# magnetorquer_board.net
KiCad netlist of a schematic drawn in EAGLE
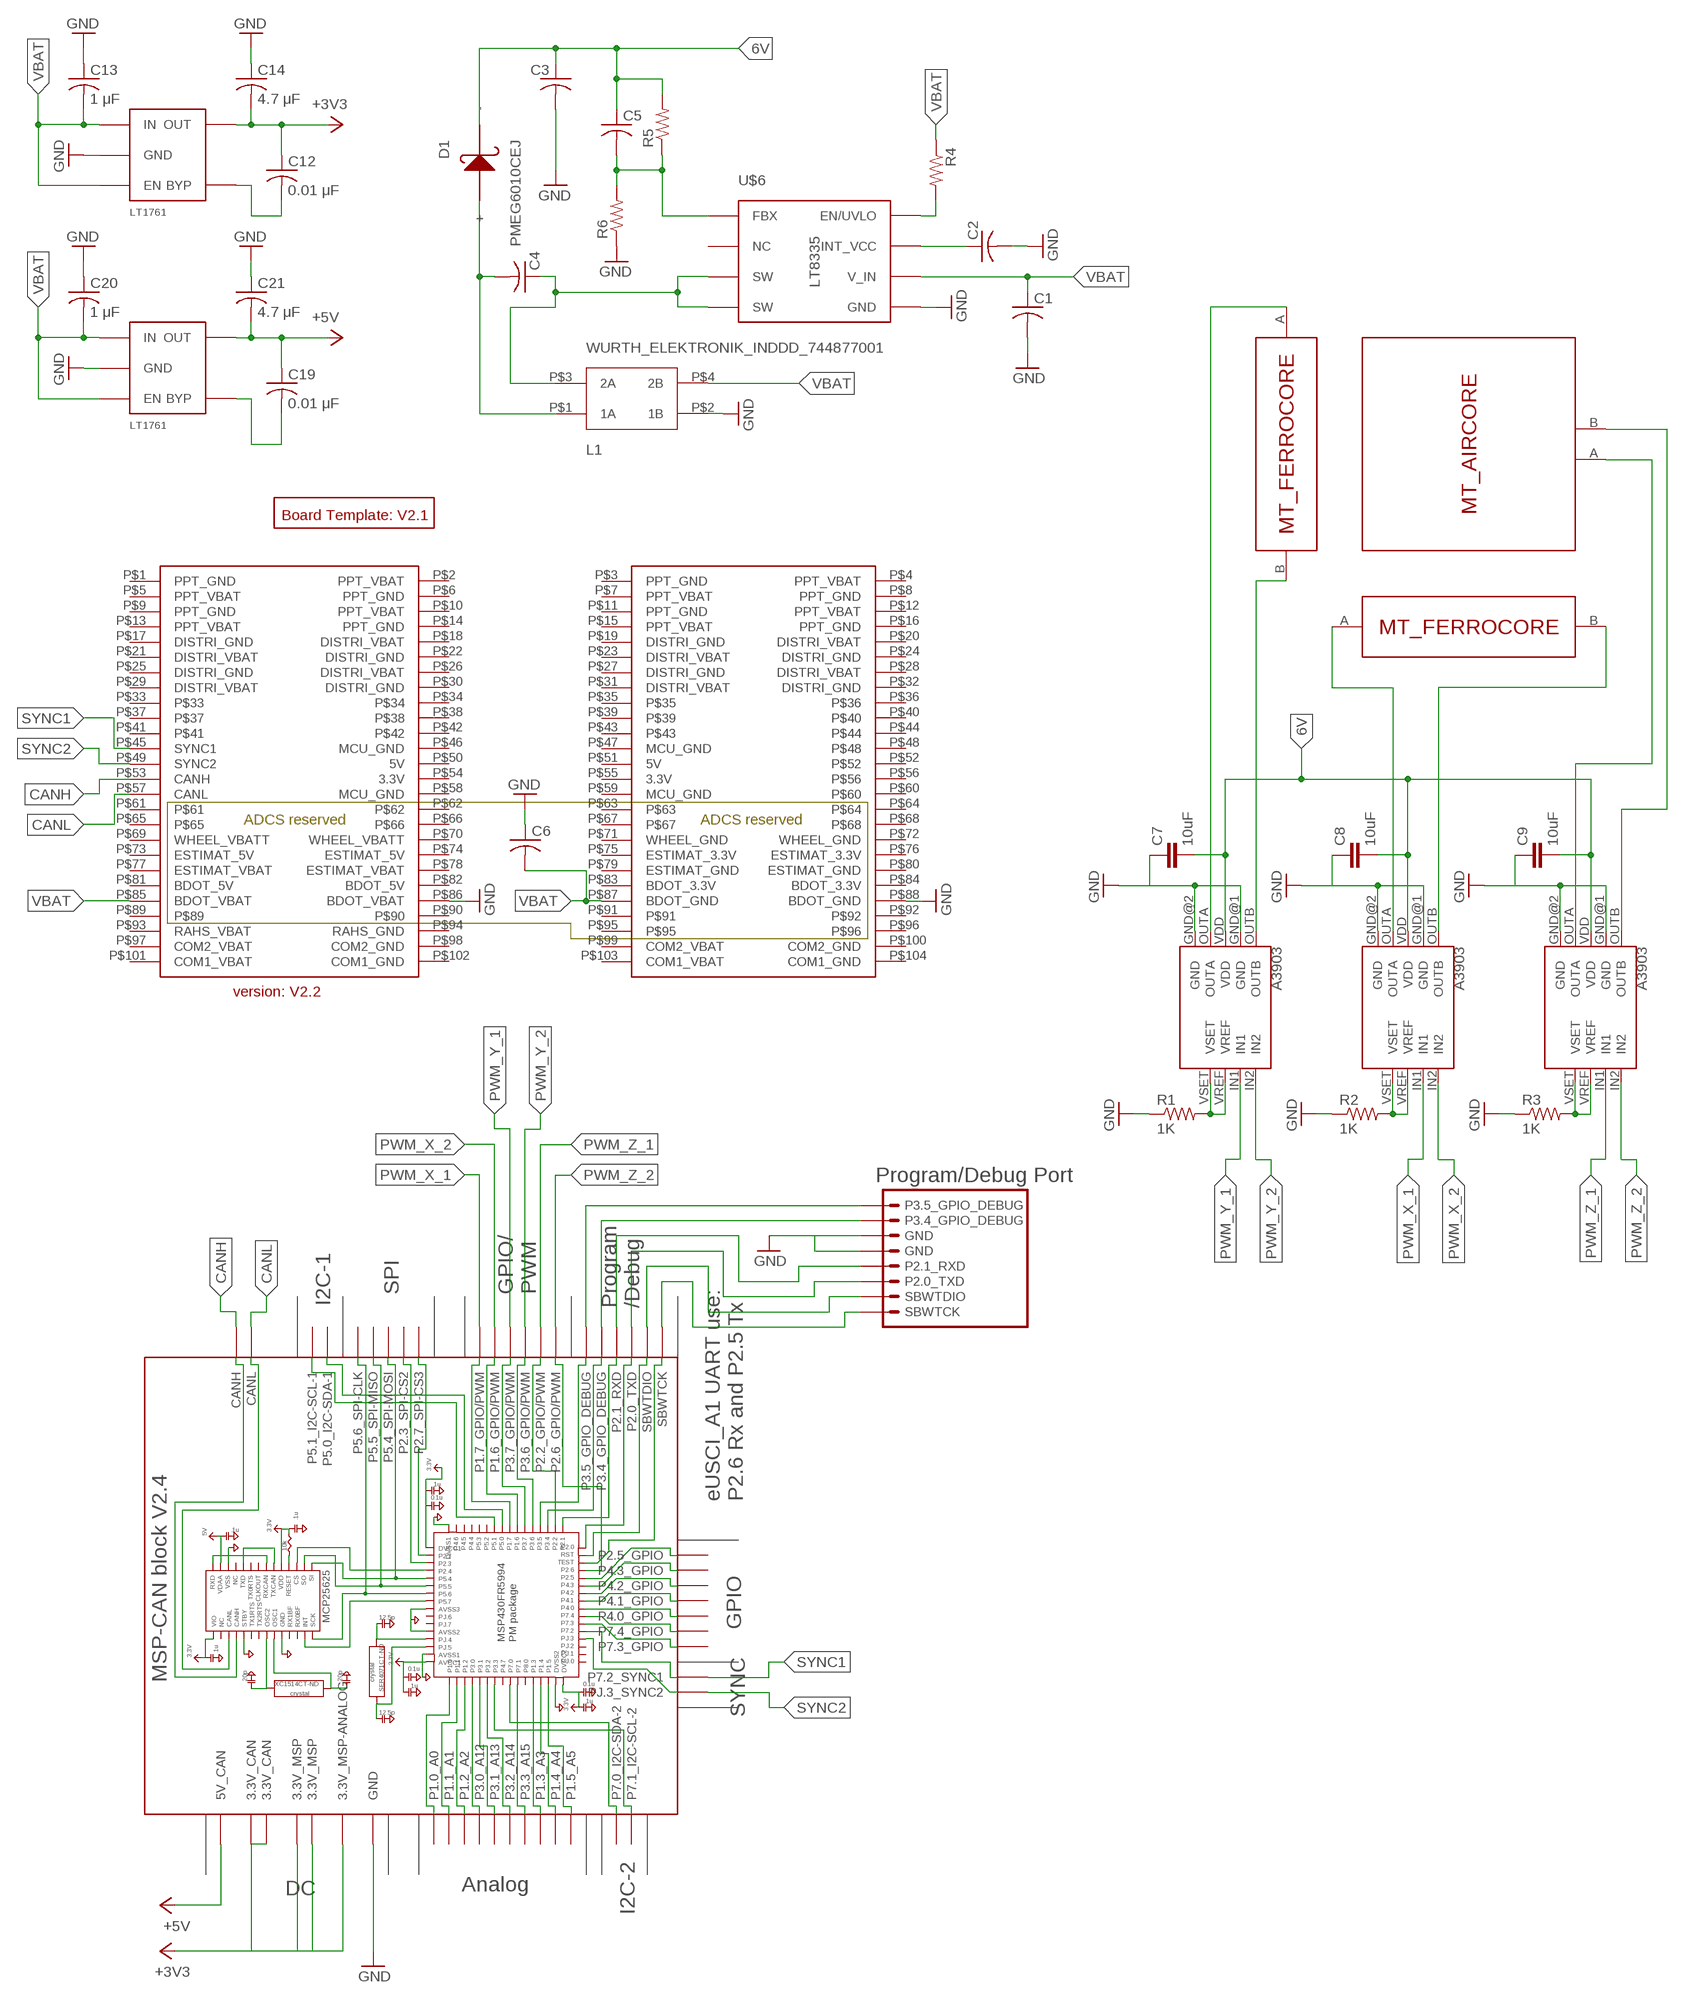
[diagram p0: schematic, sheet 1]

(export (version "E")
  (design (tool "Eeschema 10.0.6"))
  (components
    (comp (ref "C1")
      (value "C-USC0805")
      (footprint "eagle-import:C0805")
      (libsource (lib "eagle-import") (part "C-USC0805"))
    )
    (comp (ref "C2")
      (value "C-USC0805")
      (footprint "eagle-import:C0805")
      (libsource (lib "eagle-import") (part "C-USC0805"))
    )
    (comp (ref "C3")
      (value "C-USC0805")
      (footprint "eagle-import:C0805")
      (libsource (lib "eagle-import") (part "C-USC0805"))
    )
    (comp (ref "C4")
      (value "C-USC0805")
      (footprint "eagle-import:C0805")
      (libsource (lib "eagle-import") (part "C-USC0805"))
    )
    (comp (ref "C5")
      (value "C-USC0805")
      (footprint "eagle-import:C0805")
      (libsource (lib "eagle-import") (part "C-USC0805"))
    )
    (comp (ref "C6")
      (value "C-USC0805")
      (footprint "eagle-import:C0805")
      (libsource (lib "eagle-import") (part "C-USC0805"))
    )
    (comp (ref "C7")
      (value "10uF")
      (footprint "eagle-import:C0805")
      (libsource (lib "eagle-import") (part "C-EUC0805"))
    )
    (comp (ref "C8")
      (value "10uF")
      (footprint "eagle-import:C0805")
      (libsource (lib "eagle-import") (part "C-EUC0805"))
    )
    (comp (ref "C9")
      (value "10uF")
      (footprint "eagle-import:C0805")
      (libsource (lib "eagle-import") (part "C-EUC0805"))
    )
    (comp (ref "C12")
      (value "0.01 μF")
      (footprint "eagle-import:C0805")
      (libsource (lib "eagle-import") (part "C-USC0805"))
    )
    (comp (ref "C13")
      (value "1 μF")
      (footprint "eagle-import:C0805")
      (libsource (lib "eagle-import") (part "C-USC0805"))
    )
    (comp (ref "C14")
      (value "4.7 μF")
      (footprint "eagle-import:C0805")
      (libsource (lib "eagle-import") (part "C-USC0805"))
    )
    (comp (ref "C19")
      (value "0.01 μF")
      (footprint "eagle-import:C0805")
      (libsource (lib "eagle-import") (part "C-USC0805"))
    )
    (comp (ref "C20")
      (value "1 μF")
      (footprint "eagle-import:C0805")
      (libsource (lib "eagle-import") (part "C-USC0805"))
    )
    (comp (ref "C21")
      (value "4.7 μF")
      (footprint "eagle-import:C0805")
      (libsource (lib "eagle-import") (part "C-USC0805"))
    )
    (comp (ref "D1")
      (value "PMEG6010CEJ")
      (footprint "eagle-import:SC-90")
      (libsource (lib "eagle-import") (part "PMEG6010CEJ"))
    )
    (comp (ref "L1")
      (value "WURTH_ELEKTRONIK_INDDD_744877001")
      (footprint "eagle-import:WURTH_ELEKTRONIK_INDDD_744877001")
      (libsource (lib "eagle-import") (part "WURTH_ELEKTRONIK_INDDD_744877001"))
    )
    (comp (ref "LDO_3V1")
      (value "LINEAR_LDO_LT1761-X")
      (footprint "eagle-import:SOT-23-5")
      (libsource (lib "eagle-import") (part "LINEAR_LDO_LT1761-X"))
    )
    (comp (ref "LDO_5V1")
      (value "LINEAR_LDO_LT1761-X")
      (footprint "eagle-import:SOT-23-5")
      (libsource (lib "eagle-import") (part "LINEAR_LDO_LT1761-X"))
    )
    (comp (ref "R1")
      (value "1K")
      (footprint "eagle-import:R0603")
      (libsource (lib "eagle-import") (part "R-US_R0603"))
    )
    (comp (ref "R2")
      (value "1K")
      (footprint "eagle-import:R0603")
      (libsource (lib "eagle-import") (part "R-US_R0603"))
    )
    (comp (ref "R3")
      (value "1K")
      (footprint "eagle-import:R0603")
      (libsource (lib "eagle-import") (part "R-US_R0603"))
    )
    (comp (ref "R4")
      (value "R-US_R0805")
      (footprint "eagle-import:R0805")
      (libsource (lib "eagle-import") (part "R-US_R0805"))
    )
    (comp (ref "R5")
      (value "R-US_R0805")
      (footprint "eagle-import:R0805")
      (libsource (lib "eagle-import") (part "R-US_R0805"))
    )
    (comp (ref "R6")
      (value "R-US_R0805")
      (footprint "eagle-import:R0805")
      (libsource (lib "eagle-import") (part "R-US_R0805"))
    )
    (comp (ref "U$1")
      (value "PC104_CONNECTOR")
      (footprint "eagle-import:PC104_CONNECTOR")
      (libsource (lib "eagle-import") (part "PC104_CONNECTOR"))
    )
    (comp (ref "U$2")
      (value "BOARD_TEMPLATE")
      (footprint "eagle-import:BOARD_TEMPLATE")
      (libsource (lib "eagle-import") (part "BOARD_TEMPLATE"))
    )
    (comp (ref "U$3")
      (value "MT_AIRCORE")
      (footprint "eagle-import:MT_AIRCORE")
      (libsource (lib "eagle-import") (part "MT_AIRCORE"))
    )
    (comp (ref "U$4")
      (value "MT_FERROCORE")
      (footprint "eagle-import:MT_FERROCORE")
      (libsource (lib "eagle-import") (part "MT_FERROCORE"))
    )
    (comp (ref "U$5")
      (value "MT_FERROCORE")
      (footprint "eagle-import:MT_FERROCORE")
      (libsource (lib "eagle-import") (part "MT_FERROCORE"))
    )
    (comp (ref "U$6")
      (value "LT8335")
      (footprint "eagle-import:DDB")
      (libsource (lib "eagle-import") (part "LT8335"))
    )
    (comp (ref "U$7")
      (value "MSP-CAN_BLOCK")
      (footprint "eagle-import:MSP-CAN_BLOCK")
      (libsource (lib "eagle-import") (part "MSP-CAN_BLOCK"))
    )
    (comp (ref "U$8")
      (value "PROGRAM/DEBUG_PORT")
      (footprint "eagle-import:1X08_CONNECTOR")
      (libsource (lib "eagle-import") (part "PROGRAM/DEBUG_PORT"))
    )
    (comp (ref "U1")
      (value "A3903")
      (footprint "eagle-import:DFN-8EE")
      (libsource (lib "eagle-import") (part "A3903"))
    )
    (comp (ref "U2")
      (value "A3903")
      (footprint "eagle-import:DFN-8EE")
      (libsource (lib "eagle-import") (part "A3903"))
    )
    (comp (ref "U3")
      (value "A3903")
      (footprint "eagle-import:DFN-8EE")
      (libsource (lib "eagle-import") (part "A3903"))
    )
  )
  (nets
    (net (code "1") (name "+3V3") (class "Default")
      (node (ref "C12") (pin "1") (pinfunction "1_1") (pintype "passive"))
      (node (ref "C14") (pin "2") (pinfunction "2_2") (pintype "passive"))
      (node (ref "LDO_3V1") (pin "P$5") (pinfunction "OUT_P$5") (pintype "bidirectional"))
      (node (ref "U$7") (pin "3.3V@CAN1") (pinfunction "3.3V_CAN_3.3V@CAN1") (pintype "bidirectional"))
      (node (ref "U$7") (pin "3.3V@CAN2") (pinfunction "3.3V_CAN_3.3V@CAN2") (pintype "bidirectional"))
      (node (ref "U$7") (pin "3.3V@MSP1") (pinfunction "3.3V_MSP_3.3V@MSP1") (pintype "bidirectional"))
      (node (ref "U$7") (pin "3.3V@MSP2") (pinfunction "3.3V_MSP_3.3V@MSP2") (pintype "bidirectional"))
      (node (ref "U$7") (pin "3.3V_ANALOG@MSP2") (pinfunction "3.3V_MSP-ANALOG_3.3V_ANALOG@MSP2") (pintype "bidirectional"))
    )
    (net (code "2") (name "+5V") (class "Default")
      (node (ref "C19") (pin "1") (pinfunction "1_1") (pintype "passive"))
      (node (ref "C21") (pin "2") (pinfunction "2_2") (pintype "passive"))
      (node (ref "LDO_5V1") (pin "P$5") (pinfunction "OUT_P$5") (pintype "bidirectional"))
      (node (ref "U$7") (pin "5V") (pinfunction "5V_CAN_5V") (pintype "bidirectional"))
    )
    (net (code "3") (name "6V") (class "Default")
      (node (ref "C3") (pin "1") (pinfunction "1_1") (pintype "passive"))
      (node (ref "C5") (pin "1") (pinfunction "1_1") (pintype "passive"))
      (node (ref "C7") (pin "2") (pinfunction "2_2") (pintype "passive"))
      (node (ref "C8") (pin "2") (pinfunction "2_2") (pintype "passive"))
      (node (ref "C9") (pin "2") (pinfunction "2_2") (pintype "passive"))
      (node (ref "D1") (pin "P$2") (pinfunction "-_P$2") (pintype "bidirectional"))
      (node (ref "R5") (pin "2") (pinfunction "2_2") (pintype "passive"))
      (node (ref "U1") (pin "VDD") (pinfunction "VDD_VDD") (pintype "power_in"))
      (node (ref "U2") (pin "VDD") (pinfunction "VDD_VDD") (pintype "power_in"))
      (node (ref "U3") (pin "VDD") (pinfunction "VDD_VDD") (pintype "power_in"))
    )
    (net (code "4") (name "CANH") (class "Default")
      (node (ref "U$1") (pin "P$53") (pinfunction "CANH_P$53") (pintype "bidirectional"))
      (node (ref "U$7") (pin "CANH") (pinfunction "CANH_CANH") (pintype "bidirectional"))
    )
    (net (code "5") (name "CANL") (class "Default")
      (node (ref "U$1") (pin "P$57") (pinfunction "CANL_P$57") (pintype "bidirectional"))
      (node (ref "U$7") (pin "CANL") (pinfunction "CANL_CANL") (pintype "bidirectional"))
    )
    (net (code "6") (name "GND") (class "Default")
      (node (ref "C1") (pin "2") (pinfunction "2_2") (pintype "passive"))
      (node (ref "C13") (pin "1") (pinfunction "1_1") (pintype "passive"))
      (node (ref "C14") (pin "1") (pinfunction "1_1") (pintype "passive"))
      (node (ref "C2") (pin "2") (pinfunction "2_2") (pintype "passive"))
      (node (ref "C20") (pin "1") (pinfunction "1_1") (pintype "passive"))
      (node (ref "C21") (pin "1") (pinfunction "1_1") (pintype "passive"))
      (node (ref "C3") (pin "2") (pinfunction "2_2") (pintype "passive"))
      (node (ref "C6") (pin "1") (pinfunction "1_1") (pintype "passive"))
      (node (ref "C7") (pin "1") (pinfunction "1_1") (pintype "passive"))
      (node (ref "C8") (pin "1") (pinfunction "1_1") (pintype "passive"))
      (node (ref "C9") (pin "1") (pinfunction "1_1") (pintype "passive"))
      (node (ref "L1") (pin "P$2") (pinfunction "1B_P$2") (pintype "bidirectional"))
      (node (ref "LDO_3V1") (pin "P$2") (pinfunction "GND_P$2") (pintype "bidirectional"))
      (node (ref "LDO_5V1") (pin "P$2") (pinfunction "GND_P$2") (pintype "bidirectional"))
      (node (ref "R1") (pin "1") (pinfunction "1_1") (pintype "passive"))
      (node (ref "R2") (pin "1") (pinfunction "1_1") (pintype "passive"))
      (node (ref "R3") (pin "1") (pinfunction "1_1") (pintype "passive"))
      (node (ref "R6") (pin "1") (pinfunction "1_1") (pintype "passive"))
      (node (ref "U$1") (pin "P$86") (pinfunction "BDOT_VBAT_P$86") (pintype "bidirectional"))
      (node (ref "U$1") (pin "P$88") (pinfunction "BDOT_GND_P$88") (pintype "bidirectional"))
      (node (ref "U$6") (pin "GND") (pinfunction "GND_GND") (pintype "bidirectional"))
      (node (ref "U$6") (pin "P$5") (pinfunction "GND_P$5") (pintype "bidirectional"))
      (node (ref "U$7") (pin "GND@1") (pinfunction "GND_GND@1") (pintype "bidirectional"))
      (node (ref "U$7") (pin "GND@10") (pinfunction "GND_GND@10") (pintype "bidirectional"))
      (node (ref "U$7") (pin "GND@11") (pinfunction "GND_GND@11") (pintype "bidirectional"))
      (node (ref "U$7") (pin "GND@12") (pinfunction "GND_GND@12") (pintype "bidirectional"))
      (node (ref "U$7") (pin "GND@13") (pinfunction "GND_GND@13") (pintype "bidirectional"))
      (node (ref "U$7") (pin "GND@14") (pinfunction "GND_GND@14") (pintype "bidirectional"))
      (node (ref "U$7") (pin "GND@15") (pinfunction "GND_GND@15") (pintype "bidirectional"))
      (node (ref "U$7") (pin "GND@16") (pinfunction "GND_GND@16") (pintype "bidirectional"))
      (node (ref "U$7") (pin "GND@17") (pinfunction "GND_GND@17") (pintype "bidirectional"))
      (node (ref "U$7") (pin "GND@2") (pinfunction "GND_GND@2") (pintype "bidirectional"))
      (node (ref "U$7") (pin "GND@26") (pinfunction "GND_GND@26") (pintype "bidirectional"))
      (node (ref "U$7") (pin "GND@3") (pinfunction "GND_GND@3") (pintype "bidirectional"))
      (node (ref "U$7") (pin "GND@4") (pinfunction "GND_GND@4") (pintype "bidirectional"))
      (node (ref "U$7") (pin "GND@5") (pinfunction "GND_GND@5") (pintype "bidirectional"))
      (node (ref "U$7") (pin "GND@7") (pinfunction "GND_GND@7") (pintype "bidirectional"))
      (node (ref "U$7") (pin "GND@8") (pinfunction "GND_GND@8") (pintype "bidirectional"))
      (node (ref "U$7") (pin "GND@9") (pinfunction "GND_GND@9") (pintype "bidirectional"))
      (node (ref "U$8") (pin "5") (pinfunction "GND_5") (pintype "bidirectional"))
      (node (ref "U$8") (pin "6") (pinfunction "GND_6") (pintype "bidirectional"))
      (node (ref "U1") (pin "GND@1") (pinfunction "GND_GND@1") (pintype "power_in"))
      (node (ref "U1") (pin "GND@2") (pinfunction "GND_GND@2") (pintype "power_in"))
      (node (ref "U2") (pin "GND@1") (pinfunction "GND_GND@1") (pintype "power_in"))
      (node (ref "U2") (pin "GND@2") (pinfunction "GND_GND@2") (pintype "power_in"))
      (node (ref "U3") (pin "GND@1") (pinfunction "GND_GND@1") (pintype "power_in"))
      (node (ref "U3") (pin "GND@2") (pinfunction "GND_GND@2") (pintype "power_in"))
    )
    (net (code "7") (name "Net-(D1-+)") (class "Default")
      (node (ref "C4") (pin "2") (pinfunction "2_2") (pintype "passive"))
      (node (ref "D1") (pin "P$1") (pinfunction "+_P$1") (pintype "bidirectional"))
      (node (ref "L1") (pin "P$1") (pinfunction "1A_P$1") (pintype "bidirectional"))
    )
    (net (code "8") (name "Net-(L1-2A)") (class "Default")
      (node (ref "C4") (pin "1") (pinfunction "1_1") (pintype "passive"))
      (node (ref "L1") (pin "P$3") (pinfunction "2A_P$3") (pintype "bidirectional"))
      (node (ref "U$6") (pin "P$3") (pinfunction "SW_P$3") (pintype "bidirectional"))
      (node (ref "U$6") (pin "P$4") (pinfunction "SW_P$4") (pintype "bidirectional"))
    )
    (net (code "9") (name "Net-(LDO_3V1-BYP)") (class "Default")
      (node (ref "C12") (pin "2") (pinfunction "2_2") (pintype "passive"))
      (node (ref "LDO_3V1") (pin "P$4") (pinfunction "BYP_P$4") (pintype "bidirectional"))
    )
    (net (code "10") (name "Net-(LDO_5V1-BYP)") (class "Default")
      (node (ref "C19") (pin "2") (pinfunction "2_2") (pintype "passive"))
      (node (ref "LDO_5V1") (pin "P$4") (pinfunction "BYP_P$4") (pintype "bidirectional"))
    )
    (net (code "11") (name "Net-(R1-Pad2)") (class "Default")
      (node (ref "R1") (pin "2") (pinfunction "2_2") (pintype "passive"))
      (node (ref "U1") (pin "VREF") (pinfunction "VREF_VREF") (pintype "power_in"))
      (node (ref "U1") (pin "VSET") (pinfunction "VSET_VSET") (pintype "bidirectional"))
    )
    (net (code "12") (name "Net-(R2-Pad2)") (class "Default")
      (node (ref "R2") (pin "2") (pinfunction "2_2") (pintype "passive"))
      (node (ref "U2") (pin "VREF") (pinfunction "VREF_VREF") (pintype "power_in"))
      (node (ref "U2") (pin "VSET") (pinfunction "VSET_VSET") (pintype "bidirectional"))
    )
    (net (code "13") (name "Net-(R3-Pad2)") (class "Default")
      (node (ref "R3") (pin "2") (pinfunction "2_2") (pintype "passive"))
      (node (ref "U3") (pin "VREF") (pinfunction "VREF_VREF") (pintype "power_in"))
      (node (ref "U3") (pin "VSET") (pinfunction "VSET_VSET") (pintype "bidirectional"))
    )
    (net (code "14") (name "Net-(U$3-PadA)") (class "Default")
      (node (ref "U$3") (pin "A") (pinfunction "A_A") (pintype "bidirectional"))
      (node (ref "U3") (pin "OUTA") (pinfunction "OUTA_OUTA") (pintype "output"))
    )
    (net (code "15") (name "Net-(U$3-PadB)") (class "Default")
      (node (ref "U$3") (pin "B") (pinfunction "B_B") (pintype "bidirectional"))
      (node (ref "U3") (pin "OUTB") (pinfunction "OUTB_OUTB") (pintype "output"))
    )
    (net (code "16") (name "Net-(U$4-PadA)") (class "Default")
      (node (ref "U$4") (pin "A") (pinfunction "A_A") (pintype "bidirectional"))
      (node (ref "U1") (pin "OUTA") (pinfunction "OUTA_OUTA") (pintype "output"))
    )
    (net (code "17") (name "Net-(U$4-PadB)") (class "Default")
      (node (ref "U$4") (pin "B") (pinfunction "B_B") (pintype "bidirectional"))
      (node (ref "U1") (pin "OUTB") (pinfunction "OUTB_OUTB") (pintype "output"))
    )
    (net (code "18") (name "Net-(U$5-PadA)") (class "Default")
      (node (ref "U$5") (pin "A") (pinfunction "A_A") (pintype "bidirectional"))
      (node (ref "U2") (pin "OUTA") (pinfunction "OUTA_OUTA") (pintype "output"))
    )
    (net (code "19") (name "Net-(U$5-PadB)") (class "Default")
      (node (ref "U$5") (pin "B") (pinfunction "B_B") (pintype "bidirectional"))
      (node (ref "U2") (pin "OUTB") (pinfunction "OUTB_OUTB") (pintype "output"))
    )
    (net (code "20") (name "Net-(U$6-EN{slash}UVLO)") (class "Default")
      (node (ref "R4") (pin "2") (pinfunction "2_2") (pintype "passive"))
      (node (ref "U$6") (pin "P$8") (pinfunction "EN/UVLO_P$8") (pintype "bidirectional"))
    )
    (net (code "21") (name "Net-(U$6-FBX)") (class "Default")
      (node (ref "C5") (pin "2") (pinfunction "2_2") (pintype "passive"))
      (node (ref "R5") (pin "1") (pinfunction "1_1") (pintype "passive"))
      (node (ref "R6") (pin "2") (pinfunction "2_2") (pintype "passive"))
      (node (ref "U$6") (pin "P$1") (pinfunction "FBX_P$1") (pintype "bidirectional"))
    )
    (net (code "22") (name "Net-(U$6-INT_VCC)") (class "Default")
      (node (ref "C2") (pin "1") (pinfunction "1_1") (pintype "passive"))
      (node (ref "U$6") (pin "P$7") (pinfunction "INT_VCC_P$7") (pintype "bidirectional"))
    )
    (net (code "23") (name "Net-(U$7-PadSBWTCK)") (class "Default")
      (node (ref "U$7") (pin "SBWTCK") (pinfunction "SBWTCK_SBWTCK") (pintype "bidirectional"))
      (node (ref "U$8") (pin "SBWTCK") (pinfunction "SBWTCK_SBWTCK") (pintype "bidirectional"))
    )
    (net (code "24") (name "Net-(U$8-P2.0_TXD)") (class "Default")
      (node (ref "U$7") (pin "P2.0_TXD") (pinfunction "P2.0_TXD_P2.0_TXD") (pintype "bidirectional"))
      (node (ref "U$8") (pin "3") (pinfunction "P2.0_TXD_3") (pintype "bidirectional"))
    )
    (net (code "25") (name "Net-(U$8-P2.1_RXD)") (class "Default")
      (node (ref "U$7") (pin "P2.1_RXD") (pinfunction "P2.1_RXD_P2.1_RXD") (pintype "bidirectional"))
      (node (ref "U$8") (pin "4") (pinfunction "P2.1_RXD_4") (pintype "bidirectional"))
    )
    (net (code "26") (name "Net-(U$8-P3.4_GPIO_DEBUG)") (class "Default")
      (node (ref "U$7") (pin "P3.4_GPIO_DEBUG") (pinfunction "P3.4_GPIO_DEBUG_P3.4_GPIO_DEBUG") (pintype "bidirectional"))
      (node (ref "U$8") (pin "7") (pinfunction "P3.4_GPIO_DEBUG_7") (pintype "bidirectional"))
    )
    (net (code "27") (name "Net-(U$8-P3.5_GPIO_DEBUG)") (class "Default")
      (node (ref "U$7") (pin "P3.5_GPIO_DEBUG") (pinfunction "P3.5_GPIO_DEBUG_P3.5_GPIO_DEBUG") (pintype "bidirectional"))
      (node (ref "U$8") (pin "8") (pinfunction "P3.5_GPIO_DEBUG_8") (pintype "bidirectional"))
    )
    (net (code "28") (name "Net-(U$8-SBWTDIO)") (class "Default")
      (node (ref "U$7") (pin "SBWTDIO") (pinfunction "SBWTDIO_SBWTDIO") (pintype "bidirectional"))
      (node (ref "U$8") (pin "2") (pinfunction "SBWTDIO_2") (pintype "bidirectional"))
    )
    (net (code "29") (name "PWM_X_1") (class "Default")
      (node (ref "U$7") (pin "P1.7_GPIO/PWM") (pinfunction "P1.7_GPIO/PWM_P1.7_GPIO/PWM") (pintype "bidirectional"))
      (node (ref "U2") (pin "IN1") (pinfunction "IN1_IN1") (pintype "input"))
    )
    (net (code "30") (name "PWM_X_2") (class "Default")
      (node (ref "U$7") (pin "P1.6_GPIO/PWM") (pinfunction "P1.6_GPIO/PWM_P1.6_GPIO/PWM") (pintype "bidirectional"))
      (node (ref "U2") (pin "IN2") (pinfunction "IN2_IN2") (pintype "input"))
    )
    (net (code "31") (name "PWM_Y_1") (class "Default")
      (node (ref "U$7") (pin "P3.7_GPIO/PWM") (pinfunction "P3.7_GPIO/PWM_P3.7_GPIO/PWM") (pintype "bidirectional"))
      (node (ref "U1") (pin "IN1") (pinfunction "IN1_IN1") (pintype "input"))
    )
    (net (code "32") (name "PWM_Y_2") (class "Default")
      (node (ref "U$7") (pin "P3.6_GPIO/PWM") (pinfunction "P3.6_GPIO/PWM_P3.6_GPIO/PWM") (pintype "bidirectional"))
      (node (ref "U1") (pin "IN2") (pinfunction "IN2_IN2") (pintype "input"))
    )
    (net (code "33") (name "PWM_Z_1") (class "Default")
      (node (ref "U$7") (pin "P2.2_GPIO/PWM") (pinfunction "P2.2_GPIO/PWM_P2.2_GPIO/PWM") (pintype "bidirectional"))
      (node (ref "U3") (pin "IN1") (pinfunction "IN1_IN1") (pintype "input"))
    )
    (net (code "34") (name "PWM_Z_2") (class "Default")
      (node (ref "U$7") (pin "P2.6_GPIO/PWM") (pinfunction "P2.6_GPIO/PWM_P2.6_GPIO/PWM") (pintype "bidirectional"))
      (node (ref "U3") (pin "IN2") (pinfunction "IN2_IN2") (pintype "input"))
    )
    (net (code "35") (name "SYNC1") (class "Default")
      (node (ref "U$1") (pin "P$45") (pinfunction "SYNC1_P$45") (pintype "bidirectional"))
      (node (ref "U$7") (pin "P7.2_SYNC1") (pinfunction "P7.2_SYNC1_P7.2_SYNC1") (pintype "bidirectional"))
    )
    (net (code "36") (name "SYNC2") (class "Default")
      (node (ref "U$1") (pin "P$49") (pinfunction "SYNC2_P$49") (pintype "bidirectional"))
      (node (ref "U$7") (pin "PJ.3_SYNC2") (pinfunction "PJ.3_SYNC2_PJ.3_SYNC2") (pintype "bidirectional"))
    )
    (net (code "37") (name "VBAT") (class "Default")
      (node (ref "C1") (pin "1") (pinfunction "1_1") (pintype "passive"))
      (node (ref "C13") (pin "2") (pinfunction "2_2") (pintype "passive"))
      (node (ref "C20") (pin "2") (pinfunction "2_2") (pintype "passive"))
      (node (ref "C6") (pin "2") (pinfunction "2_2") (pintype "passive"))
      (node (ref "L1") (pin "P$4") (pinfunction "2B_P$4") (pintype "bidirectional"))
      (node (ref "LDO_3V1") (pin "P$1") (pinfunction "IN_P$1") (pintype "bidirectional"))
      (node (ref "LDO_3V1") (pin "P$3") (pinfunction "EN_P$3") (pintype "bidirectional"))
      (node (ref "LDO_5V1") (pin "P$1") (pinfunction "IN_P$1") (pintype "bidirectional"))
      (node (ref "LDO_5V1") (pin "P$3") (pinfunction "EN_P$3") (pintype "bidirectional"))
      (node (ref "R4") (pin "1") (pinfunction "1_1") (pintype "passive"))
      (node (ref "U$1") (pin "P$85") (pinfunction "BDOT_VBAT_P$85") (pintype "bidirectional"))
      (node (ref "U$1") (pin "P$87") (pinfunction "BDOT_GND_P$87") (pintype "bidirectional"))
      (node (ref "U$6") (pin "P$6") (pinfunction "V_IN_P$6") (pintype "bidirectional"))
    )
    (net (code "38") (name "unconnected-(U$1-3.3V-PadP$54)") (class "Default")
      (node (ref "U$1") (pin "P$54") (pinfunction "3.3V_P$54") (pintype "bidirectional"))
    )
    (net (code "39") (name "unconnected-(U$1-3.3V-PadP$55)") (class "Default")
      (node (ref "U$1") (pin "P$55") (pinfunction "3.3V_P$55") (pintype "bidirectional"))
    )
    (net (code "40") (name "unconnected-(U$1-5V-PadP$50)") (class "Default")
      (node (ref "U$1") (pin "P$50") (pinfunction "5V_P$50") (pintype "bidirectional"))
    )
    (net (code "41") (name "unconnected-(U$1-5V-PadP$51)") (class "Default")
      (node (ref "U$1") (pin "P$51") (pinfunction "5V_P$51") (pintype "bidirectional"))
    )
    (net (code "42") (name "unconnected-(U$1-BDOT_3.3V-PadP$83)") (class "Default")
      (node (ref "U$1") (pin "P$83") (pinfunction "BDOT_3.3V_P$83") (pintype "bidirectional"))
    )
    (net (code "43") (name "unconnected-(U$1-BDOT_3.3V-PadP$84)") (class "Default")
      (node (ref "U$1") (pin "P$84") (pinfunction "BDOT_3.3V_P$84") (pintype "bidirectional"))
    )
    (net (code "44") (name "unconnected-(U$1-BDOT_5V-PadP$81)") (class "Default")
      (node (ref "U$1") (pin "P$81") (pinfunction "BDOT_5V_P$81") (pintype "bidirectional"))
    )
    (net (code "45") (name "unconnected-(U$1-BDOT_5V-PadP$82)") (class "Default")
      (node (ref "U$1") (pin "P$82") (pinfunction "BDOT_5V_P$82") (pintype "bidirectional"))
    )
    (net (code "46") (name "unconnected-(U$1-COM1_GND-PadP$102)") (class "Default")
      (node (ref "U$1") (pin "P$102") (pinfunction "COM1_GND_P$102") (pintype "bidirectional"))
    )
    (net (code "47") (name "unconnected-(U$1-COM1_GND-PadP$104)") (class "Default")
      (node (ref "U$1") (pin "P$104") (pinfunction "COM1_GND_P$104") (pintype "bidirectional"))
    )
    (net (code "48") (name "unconnected-(U$1-COM1_VBAT-PadP$101)") (class "Default")
      (node (ref "U$1") (pin "P$101") (pinfunction "COM1_VBAT_P$101") (pintype "bidirectional"))
    )
    (net (code "49") (name "unconnected-(U$1-COM1_VBAT-PadP$103)") (class "Default")
      (node (ref "U$1") (pin "P$103") (pinfunction "COM1_VBAT_P$103") (pintype "bidirectional"))
    )
    (net (code "50") (name "unconnected-(U$1-COM2_GND-PadP$98)") (class "Default")
      (node (ref "U$1") (pin "P$98") (pinfunction "COM2_GND_P$98") (pintype "bidirectional"))
    )
    (net (code "51") (name "unconnected-(U$1-COM2_GND-PadP$100)") (class "Default")
      (node (ref "U$1") (pin "P$100") (pinfunction "COM2_GND_P$100") (pintype "bidirectional"))
    )
    (net (code "52") (name "unconnected-(U$1-COM2_VBAT-PadP$97)") (class "Default")
      (node (ref "U$1") (pin "P$97") (pinfunction "COM2_VBAT_P$97") (pintype "bidirectional"))
    )
    (net (code "53") (name "unconnected-(U$1-COM2_VBAT-PadP$99)") (class "Default")
      (node (ref "U$1") (pin "P$99") (pinfunction "COM2_VBAT_P$99") (pintype "bidirectional"))
    )
    (net (code "54") (name "unconnected-(U$1-DISTRI_GND-PadP$17)") (class "Default")
      (node (ref "U$1") (pin "P$17") (pinfunction "DISTRI_GND_P$17") (pintype "bidirectional"))
    )
    (net (code "55") (name "unconnected-(U$1-DISTRI_GND-PadP$19)") (class "Default")
      (node (ref "U$1") (pin "P$19") (pinfunction "DISTRI_GND_P$19") (pintype "bidirectional"))
    )
    (net (code "56") (name "unconnected-(U$1-DISTRI_GND-PadP$22)") (class "Default")
      (node (ref "U$1") (pin "P$22") (pinfunction "DISTRI_GND_P$22") (pintype "bidirectional"))
    )
    (net (code "57") (name "unconnected-(U$1-DISTRI_GND-PadP$24)") (class "Default")
      (node (ref "U$1") (pin "P$24") (pinfunction "DISTRI_GND_P$24") (pintype "bidirectional"))
    )
    (net (code "58") (name "unconnected-(U$1-DISTRI_GND-PadP$25)") (class "Default")
      (node (ref "U$1") (pin "P$25") (pinfunction "DISTRI_GND_P$25") (pintype "bidirectional"))
    )
    (net (code "59") (name "unconnected-(U$1-DISTRI_GND-PadP$27)") (class "Default")
      (node (ref "U$1") (pin "P$27") (pinfunction "DISTRI_GND_P$27") (pintype "bidirectional"))
    )
    (net (code "60") (name "unconnected-(U$1-DISTRI_GND-PadP$30)") (class "Default")
      (node (ref "U$1") (pin "P$30") (pinfunction "DISTRI_GND_P$30") (pintype "bidirectional"))
    )
    (net (code "61") (name "unconnected-(U$1-DISTRI_GND-PadP$32)") (class "Default")
      (node (ref "U$1") (pin "P$32") (pinfunction "DISTRI_GND_P$32") (pintype "bidirectional"))
    )
    (net (code "62") (name "unconnected-(U$1-DISTRI_VBAT-PadP$18)") (class "Default")
      (node (ref "U$1") (pin "P$18") (pinfunction "DISTRI_VBAT_P$18") (pintype "bidirectional"))
    )
    (net (code "63") (name "unconnected-(U$1-DISTRI_VBAT-PadP$20)") (class "Default")
      (node (ref "U$1") (pin "P$20") (pinfunction "DISTRI_VBAT_P$20") (pintype "bidirectional"))
    )
    (net (code "64") (name "unconnected-(U$1-DISTRI_VBAT-PadP$21)") (class "Default")
      (node (ref "U$1") (pin "P$21") (pinfunction "DISTRI_VBAT_P$21") (pintype "bidirectional"))
    )
    (net (code "65") (name "unconnected-(U$1-DISTRI_VBAT-PadP$23)") (class "Default")
      (node (ref "U$1") (pin "P$23") (pinfunction "DISTRI_VBAT_P$23") (pintype "bidirectional"))
    )
    (net (code "66") (name "unconnected-(U$1-DISTRI_VBAT-PadP$26)") (class "Default")
      (node (ref "U$1") (pin "P$26") (pinfunction "DISTRI_VBAT_P$26") (pintype "bidirectional"))
    )
    (net (code "67") (name "unconnected-(U$1-DISTRI_VBAT-PadP$28)") (class "Default")
      (node (ref "U$1") (pin "P$28") (pinfunction "DISTRI_VBAT_P$28") (pintype "bidirectional"))
    )
    (net (code "68") (name "unconnected-(U$1-DISTRI_VBAT-PadP$29)") (class "Default")
      (node (ref "U$1") (pin "P$29") (pinfunction "DISTRI_VBAT_P$29") (pintype "bidirectional"))
    )
    (net (code "69") (name "unconnected-(U$1-DISTRI_VBAT-PadP$31)") (class "Default")
      (node (ref "U$1") (pin "P$31") (pinfunction "DISTRI_VBAT_P$31") (pintype "bidirectional"))
    )
    (net (code "70") (name "unconnected-(U$1-ESTIMAT_3.3V-PadP$75)") (class "Default")
      (node (ref "U$1") (pin "P$75") (pinfunction "ESTIMAT_3.3V_P$75") (pintype "bidirectional"))
    )
    (net (code "71") (name "unconnected-(U$1-ESTIMAT_3.3V-PadP$76)") (class "Default")
      (node (ref "U$1") (pin "P$76") (pinfunction "ESTIMAT_3.3V_P$76") (pintype "bidirectional"))
    )
    (net (code "72") (name "unconnected-(U$1-ESTIMAT_5V-PadP$73)") (class "Default")
      (node (ref "U$1") (pin "P$73") (pinfunction "ESTIMAT_5V_P$73") (pintype "bidirectional"))
    )
    (net (code "73") (name "unconnected-(U$1-ESTIMAT_5V-PadP$74)") (class "Default")
      (node (ref "U$1") (pin "P$74") (pinfunction "ESTIMAT_5V_P$74") (pintype "bidirectional"))
    )
    (net (code "74") (name "unconnected-(U$1-ESTIMAT_GND-PadP$79)") (class "Default")
      (node (ref "U$1") (pin "P$79") (pinfunction "ESTIMAT_GND_P$79") (pintype "bidirectional"))
    )
    (net (code "75") (name "unconnected-(U$1-ESTIMAT_GND-PadP$80)") (class "Default")
      (node (ref "U$1") (pin "P$80") (pinfunction "ESTIMAT_GND_P$80") (pintype "bidirectional"))
    )
    (net (code "76") (name "unconnected-(U$1-ESTIMAT_VBAT-PadP$77)") (class "Default")
      (node (ref "U$1") (pin "P$77") (pinfunction "ESTIMAT_VBAT_P$77") (pintype "bidirectional"))
    )
    (net (code "77") (name "unconnected-(U$1-ESTIMAT_VBAT-PadP$78)") (class "Default")
      (node (ref "U$1") (pin "P$78") (pinfunction "ESTIMAT_VBAT_P$78") (pintype "bidirectional"))
    )
    (net (code "78") (name "unconnected-(U$1-MCU_GND-PadP$46)") (class "Default")
      (node (ref "U$1") (pin "P$46") (pinfunction "MCU_GND_P$46") (pintype "bidirectional"))
    )
    (net (code "79") (name "unconnected-(U$1-MCU_GND-PadP$47)") (class "Default")
      (node (ref "U$1") (pin "P$47") (pinfunction "MCU_GND_P$47") (pintype "bidirectional"))
    )
    (net (code "80") (name "unconnected-(U$1-MCU_GND-PadP$58)") (class "Default")
      (node (ref "U$1") (pin "P$58") (pinfunction "MCU_GND_P$58") (pintype "bidirectional"))
    )
    (net (code "81") (name "unconnected-(U$1-MCU_GND-PadP$59)") (class "Default")
      (node (ref "U$1") (pin "P$59") (pinfunction "MCU_GND_P$59") (pintype "bidirectional"))
    )
    (net (code "82") (name "unconnected-(U$1-PPT_GND-PadP$1)") (class "Default")
      (node (ref "U$1") (pin "P$1") (pinfunction "PPT_GND_P$1") (pintype "bidirectional"))
    )
    (net (code "83") (name "unconnected-(U$1-PPT_GND-PadP$3)") (class "Default")
      (node (ref "U$1") (pin "P$3") (pinfunction "PPT_GND_P$3") (pintype "bidirectional"))
    )
    (net (code "84") (name "unconnected-(U$1-PPT_GND-PadP$6)") (class "Default")
      (node (ref "U$1") (pin "P$6") (pinfunction "PPT_GND_P$6") (pintype "bidirectional"))
    )
    (net (code "85") (name "unconnected-(U$1-PPT_GND-PadP$8)") (class "Default")
      (node (ref "U$1") (pin "P$8") (pinfunction "PPT_GND_P$8") (pintype "bidirectional"))
    )
    (net (code "86") (name "unconnected-(U$1-PPT_GND-PadP$9)") (class "Default")
      (node (ref "U$1") (pin "P$9") (pinfunction "PPT_GND_P$9") (pintype "bidirectional"))
    )
    (net (code "87") (name "unconnected-(U$1-PPT_GND-PadP$11)") (class "Default")
      (node (ref "U$1") (pin "P$11") (pinfunction "PPT_GND_P$11") (pintype "bidirectional"))
    )
    (net (code "88") (name "unconnected-(U$1-PPT_GND-PadP$14)") (class "Default")
      (node (ref "U$1") (pin "P$14") (pinfunction "PPT_GND_P$14") (pintype "bidirectional"))
    )
    (net (code "89") (name "unconnected-(U$1-PPT_GND-PadP$16)") (class "Default")
      (node (ref "U$1") (pin "P$16") (pinfunction "PPT_GND_P$16") (pintype "bidirectional"))
    )
    (net (code "90") (name "unconnected-(U$1-PPT_VBAT-PadP$2)") (class "Default")
      (node (ref "U$1") (pin "P$2") (pinfunction "PPT_VBAT_P$2") (pintype "bidirectional"))
    )
    (net (code "91") (name "unconnected-(U$1-PPT_VBAT-PadP$4)") (class "Default")
      (node (ref "U$1") (pin "P$4") (pinfunction "PPT_VBAT_P$4") (pintype "bidirectional"))
    )
    (net (code "92") (name "unconnected-(U$1-PPT_VBAT-PadP$5)") (class "Default")
      (node (ref "U$1") (pin "P$5") (pinfunction "PPT_VBAT_P$5") (pintype "bidirectional"))
    )
    (net (code "93") (name "unconnected-(U$1-PPT_VBAT-PadP$7)") (class "Default")
      (node (ref "U$1") (pin "P$7") (pinfunction "PPT_VBAT_P$7") (pintype "bidirectional"))
    )
    (net (code "94") (name "unconnected-(U$1-PPT_VBAT-PadP$10)") (class "Default")
      (node (ref "U$1") (pin "P$10") (pinfunction "PPT_VBAT_P$10") (pintype "bidirectional"))
    )
    (net (code "95") (name "unconnected-(U$1-PPT_VBAT-PadP$12)") (class "Default")
      (node (ref "U$1") (pin "P$12") (pinfunction "PPT_VBAT_P$12") (pintype "bidirectional"))
    )
    (net (code "96") (name "unconnected-(U$1-PPT_VBAT-PadP$13)") (class "Default")
      (node (ref "U$1") (pin "P$13") (pinfunction "PPT_VBAT_P$13") (pintype "bidirectional"))
    )
    (net (code "97") (name "unconnected-(U$1-PPT_VBAT-PadP$15)") (class "Default")
      (node (ref "U$1") (pin "P$15") (pinfunction "PPT_VBAT_P$15") (pintype "bidirectional"))
    )
    (net (code "98") (name "unconnected-(U$1-PadP$33)") (class "Default")
      (node (ref "U$1") (pin "P$33") (pinfunction "P$33_P$33") (pintype "bidirectional"))
    )
    (net (code "99") (name "unconnected-(U$1-PadP$34)") (class "Default")
      (node (ref "U$1") (pin "P$34") (pinfunction "P$34_P$34") (pintype "bidirectional"))
    )
    (net (code "100") (name "unconnected-(U$1-PadP$35)") (class "Default")
      (node (ref "U$1") (pin "P$35") (pinfunction "P$35_P$35") (pintype "bidirectional"))
    )
    (net (code "101") (name "unconnected-(U$1-PadP$36)") (class "Default")
      (node (ref "U$1") (pin "P$36") (pinfunction "P$36_P$36") (pintype "bidirectional"))
    )
    (net (code "102") (name "unconnected-(U$1-PadP$37)") (class "Default")
      (node (ref "U$1") (pin "P$37") (pinfunction "P$37_P$37") (pintype "bidirectional"))
    )
    (net (code "103") (name "unconnected-(U$1-PadP$38)") (class "Default")
      (node (ref "U$1") (pin "P$38") (pinfunction "P$38_P$38") (pintype "bidirectional"))
    )
    (net (code "104") (name "unconnected-(U$1-PadP$39)") (class "Default")
      (node (ref "U$1") (pin "P$39") (pinfunction "P$39_P$39") (pintype "bidirectional"))
    )
    (net (code "105") (name "unconnected-(U$1-PadP$40)") (class "Default")
      (node (ref "U$1") (pin "P$40") (pinfunction "P$40_P$40") (pintype "bidirectional"))
    )
    (net (code "106") (name "unconnected-(U$1-PadP$41)") (class "Default")
      (node (ref "U$1") (pin "P$41") (pinfunction "P$41_P$41") (pintype "bidirectional"))
    )
    (net (code "107") (name "unconnected-(U$1-PadP$42)") (class "Default")
      (node (ref "U$1") (pin "P$42") (pinfunction "P$42_P$42") (pintype "bidirectional"))
    )
    (net (code "108") (name "unconnected-(U$1-PadP$43)") (class "Default")
      (node (ref "U$1") (pin "P$43") (pinfunction "P$43_P$43") (pintype "bidirectional"))
    )
    (net (code "109") (name "unconnected-(U$1-PadP$44)") (class "Default")
      (node (ref "U$1") (pin "P$44") (pinfunction "P$44_P$44") (pintype "bidirectional"))
    )
    (net (code "110") (name "unconnected-(U$1-PadP$48)") (class "Default")
      (node (ref "U$1") (pin "P$48") (pinfunction "P$48_P$48") (pintype "bidirectional"))
    )
    (net (code "111") (name "unconnected-(U$1-PadP$52)") (class "Default")
      (node (ref "U$1") (pin "P$52") (pinfunction "P$52_P$52") (pintype "bidirectional"))
    )
    (net (code "112") (name "unconnected-(U$1-PadP$56)") (class "Default")
      (node (ref "U$1") (pin "P$56") (pinfunction "P$56_P$56") (pintype "bidirectional"))
    )
    (net (code "113") (name "unconnected-(U$1-PadP$60)") (class "Default")
      (node (ref "U$1") (pin "P$60") (pinfunction "P$60_P$60") (pintype "bidirectional"))
    )
    (net (code "114") (name "unconnected-(U$1-PadP$61)") (class "Default")
      (node (ref "U$1") (pin "P$61") (pinfunction "P$61_P$61") (pintype "bidirectional"))
    )
    (net (code "115") (name "unconnected-(U$1-PadP$62)") (class "Default")
      (node (ref "U$1") (pin "P$62") (pinfunction "P$62_P$62") (pintype "bidirectional"))
    )
    (net (code "116") (name "unconnected-(U$1-PadP$63)") (class "Default")
      (node (ref "U$1") (pin "P$63") (pinfunction "P$63_P$63") (pintype "bidirectional"))
    )
    (net (code "117") (name "unconnected-(U$1-PadP$64)") (class "Default")
      (node (ref "U$1") (pin "P$64") (pinfunction "P$64_P$64") (pintype "bidirectional"))
    )
    (net (code "118") (name "unconnected-(U$1-PadP$65)") (class "Default")
      (node (ref "U$1") (pin "P$65") (pinfunction "P$65_P$65") (pintype "bidirectional"))
    )
    (net (code "119") (name "unconnected-(U$1-PadP$66)") (class "Default")
      (node (ref "U$1") (pin "P$66") (pinfunction "P$66_P$66") (pintype "bidirectional"))
    )
    (net (code "120") (name "unconnected-(U$1-PadP$67)") (class "Default")
      (node (ref "U$1") (pin "P$67") (pinfunction "P$67_P$67") (pintype "bidirectional"))
    )
    (net (code "121") (name "unconnected-(U$1-PadP$68)") (class "Default")
      (node (ref "U$1") (pin "P$68") (pinfunction "P$68_P$68") (pintype "bidirectional"))
    )
    (net (code "122") (name "unconnected-(U$1-PadP$89)") (class "Default")
      (node (ref "U$1") (pin "P$89") (pinfunction "P$89_P$89") (pintype "bidirectional"))
    )
    (net (code "123") (name "unconnected-(U$1-PadP$90)") (class "Default")
      (node (ref "U$1") (pin "P$90") (pinfunction "P$90_P$90") (pintype "bidirectional"))
    )
    (net (code "124") (name "unconnected-(U$1-PadP$91)") (class "Default")
      (node (ref "U$1") (pin "P$91") (pinfunction "P$91_P$91") (pintype "bidirectional"))
    )
    (net (code "125") (name "unconnected-(U$1-PadP$92)") (class "Default")
      (node (ref "U$1") (pin "P$92") (pinfunction "P$92_P$92") (pintype "bidirectional"))
    )
    (net (code "126") (name "unconnected-(U$1-PadP$95)") (class "Default")
      (node (ref "U$1") (pin "P$95") (pinfunction "P$95_P$95") (pintype "bidirectional"))
    )
    (net (code "127") (name "unconnected-(U$1-PadP$96)") (class "Default")
      (node (ref "U$1") (pin "P$96") (pinfunction "P$96_P$96") (pintype "bidirectional"))
    )
    (net (code "128") (name "unconnected-(U$1-RAHS_GND-PadP$94)") (class "Default")
      (node (ref "U$1") (pin "P$94") (pinfunction "RAHS_GND_P$94") (pintype "bidirectional"))
    )
    (net (code "129") (name "unconnected-(U$1-RAHS_VBAT-PadP$93)") (class "Default")
      (node (ref "U$1") (pin "P$93") (pinfunction "RAHS_VBAT_P$93") (pintype "bidirectional"))
    )
    (net (code "130") (name "unconnected-(U$1-WHEEL_GND-PadP$71)") (class "Default")
      (node (ref "U$1") (pin "P$71") (pinfunction "WHEEL_GND_P$71") (pintype "bidirectional"))
    )
    (net (code "131") (name "unconnected-(U$1-WHEEL_GND-PadP$72)") (class "Default")
      (node (ref "U$1") (pin "P$72") (pinfunction "WHEEL_GND_P$72") (pintype "bidirectional"))
    )
    (net (code "132") (name "unconnected-(U$1-WHEEL_VBATT-PadP$69)") (class "Default")
      (node (ref "U$1") (pin "P$69") (pinfunction "WHEEL_VBATT_P$69") (pintype "bidirectional"))
    )
    (net (code "133") (name "unconnected-(U$1-WHEEL_VBATT-PadP$70)") (class "Default")
      (node (ref "U$1") (pin "P$70") (pinfunction "WHEEL_VBATT_P$70") (pintype "bidirectional"))
    )
    (net (code "134") (name "unconnected-(U$6-NC-PadP$2)") (class "Default")
      (node (ref "U$6") (pin "P$2") (pinfunction "NC_P$2") (pintype "bidirectional"))
    )
    (net (code "135") (name "unconnected-(U$7-P2.3_SPI-CS2-PadP2.4_SPI-CS2)") (class "Default")
      (node (ref "U$7") (pin "P2.4_SPI-CS2") (pinfunction "P2.3_SPI-CS2_P2.4_SPI-CS2") (pintype "bidirectional"))
    )
    (net (code "136") (name "unconnected-(U$7-PadP1.0_A0)") (class "Default")
      (node (ref "U$7") (pin "P1.0_A0") (pinfunction "P1.0_A0_P1.0_A0") (pintype "bidirectional"))
    )
    (net (code "137") (name "unconnected-(U$7-PadP1.1_A1)") (class "Default")
      (node (ref "U$7") (pin "P1.1_A1") (pinfunction "P1.1_A1_P1.1_A1") (pintype "bidirectional"))
    )
    (net (code "138") (name "unconnected-(U$7-PadP1.2_A2)") (class "Default")
      (node (ref "U$7") (pin "P1.2_A2") (pinfunction "P1.2_A2_P1.2_A2") (pintype "bidirectional"))
    )
    (net (code "139") (name "unconnected-(U$7-PadP1.3_A3)") (class "Default")
      (node (ref "U$7") (pin "P1.3_A3") (pinfunction "P1.3_A3_P1.3_A3") (pintype "bidirectional"))
    )
    (net (code "140") (name "unconnected-(U$7-PadP1.4_A4)") (class "Default")
      (node (ref "U$7") (pin "P1.4_A4") (pinfunction "P1.4_A4_P1.4_A4") (pintype "bidirectional"))
    )
    (net (code "141") (name "unconnected-(U$7-PadP1.5_A5)") (class "Default")
      (node (ref "U$7") (pin "P1.5_A5") (pinfunction "P1.5_A5_P1.5_A5") (pintype "bidirectional"))
    )
    (net (code "142") (name "unconnected-(U$7-PadP2.5_GPIO)") (class "Default")
      (node (ref "U$7") (pin "P2.5_GPIO") (pinfunction "P2.5_GPIO_P2.5_GPIO") (pintype "bidirectional"))
    )
    (net (code "143") (name "unconnected-(U$7-PadP2.7_SPI-CS3)") (class "Default")
      (node (ref "U$7") (pin "P2.7_SPI-CS3") (pinfunction "P2.7_SPI-CS3_P2.7_SPI-CS3") (pintype "bidirectional"))
    )
    (net (code "144") (name "unconnected-(U$7-PadP3.0_A12)") (class "Default")
      (node (ref "U$7") (pin "P3.0_A12") (pinfunction "P3.0_A12_P3.0_A12") (pintype "bidirectional"))
    )
    (net (code "145") (name "unconnected-(U$7-PadP3.1_A13)") (class "Default")
      (node (ref "U$7") (pin "P3.1_A13") (pinfunction "P3.1_A13_P3.1_A13") (pintype "bidirectional"))
    )
    (net (code "146") (name "unconnected-(U$7-PadP3.2_A14)") (class "Default")
      (node (ref "U$7") (pin "P3.2_A14") (pinfunction "P3.2_A14_P3.2_A14") (pintype "bidirectional"))
    )
    (net (code "147") (name "unconnected-(U$7-PadP3.3_A15)") (class "Default")
      (node (ref "U$7") (pin "P3.3_A15") (pinfunction "P3.3_A15_P3.3_A15") (pintype "bidirectional"))
    )
    (net (code "148") (name "unconnected-(U$7-PadP4.0_GPIO)") (class "Default")
      (node (ref "U$7") (pin "P4.0_GPIO") (pinfunction "P4.0_GPIO_P4.0_GPIO") (pintype "bidirectional"))
    )
    (net (code "149") (name "unconnected-(U$7-PadP4.1_GPIO)") (class "Default")
      (node (ref "U$7") (pin "P4.1_GPIO") (pinfunction "P4.1_GPIO_P4.1_GPIO") (pintype "bidirectional"))
    )
    (net (code "150") (name "unconnected-(U$7-PadP4.2_GPIO)") (class "Default")
      (node (ref "U$7") (pin "P4.2_GPIO") (pinfunction "P4.2_GPIO_P4.2_GPIO") (pintype "bidirectional"))
    )
    (net (code "151") (name "unconnected-(U$7-PadP4.3_GPIO)") (class "Default")
      (node (ref "U$7") (pin "P4.3_GPIO") (pinfunction "P4.3_GPIO_P4.3_GPIO") (pintype "bidirectional"))
    )
    (net (code "152") (name "unconnected-(U$7-PadP5.0_I2C-SDA-1)") (class "Default")
      (node (ref "U$7") (pin "P5.0_I2C-SDA-1") (pinfunction "P5.0_I2C-SDA-1_P5.0_I2C-SDA-1") (pintype "bidirectional"))
    )
    (net (code "153") (name "unconnected-(U$7-PadP5.1_I2C-SCL-1)") (class "Default")
      (node (ref "U$7") (pin "P5.1_I2C-SCL-1") (pinfunction "P5.1_I2C-SCL-1_P5.1_I2C-SCL-1") (pintype "bidirectional"))
    )
    (net (code "154") (name "unconnected-(U$7-PadP5.4_SPI-MOSI)") (class "Default")
      (node (ref "U$7") (pin "P5.4_SPI-MOSI") (pinfunction "P5.4_SPI-MOSI_P5.4_SPI-MOSI") (pintype "bidirectional"))
    )
    (net (code "155") (name "unconnected-(U$7-PadP5.5_SPI-MISO)") (class "Default")
      (node (ref "U$7") (pin "P5.5_SPI-MISO") (pinfunction "P5.5_SPI-MISO_P5.5_SPI-MISO") (pintype "bidirectional"))
    )
    (net (code "156") (name "unconnected-(U$7-PadP5.6_SPI-CLK)") (class "Default")
      (node (ref "U$7") (pin "P5.6_SPI-CLK") (pinfunction "P5.6_SPI-CLK_P5.6_SPI-CLK") (pintype "bidirectional"))
    )
    (net (code "157") (name "unconnected-(U$7-PadP7.0_I2C-SDA-2)") (class "Default")
      (node (ref "U$7") (pin "P7.0_I2C-SDA-2") (pinfunction "P7.0_I2C-SDA-2_P7.0_I2C-SDA-2") (pintype "bidirectional"))
    )
    (net (code "158") (name "unconnected-(U$7-PadP7.1_I2C-SCL-2)") (class "Default")
      (node (ref "U$7") (pin "P7.1_I2C-SCL-2") (pinfunction "P7.1_I2C-SCL-2_P7.1_I2C-SCL-2") (pintype "bidirectional"))
    )
    (net (code "159") (name "unconnected-(U$7-PadP7.3_GPIO)") (class "Default")
      (node (ref "U$7") (pin "P7.3_GPIO") (pinfunction "P7.3_GPIO_P7.3_GPIO") (pintype "bidirectional"))
    )
    (net (code "160") (name "unconnected-(U$7-PadP7.4_GPIO)") (class "Default")
      (node (ref "U$7") (pin "P7.4_GPIO") (pinfunction "P7.4_GPIO_P7.4_GPIO") (pintype "bidirectional"))
    )
  )
)
